# hw2.net
KiCad netlist of a schematic drawn in EAGLE
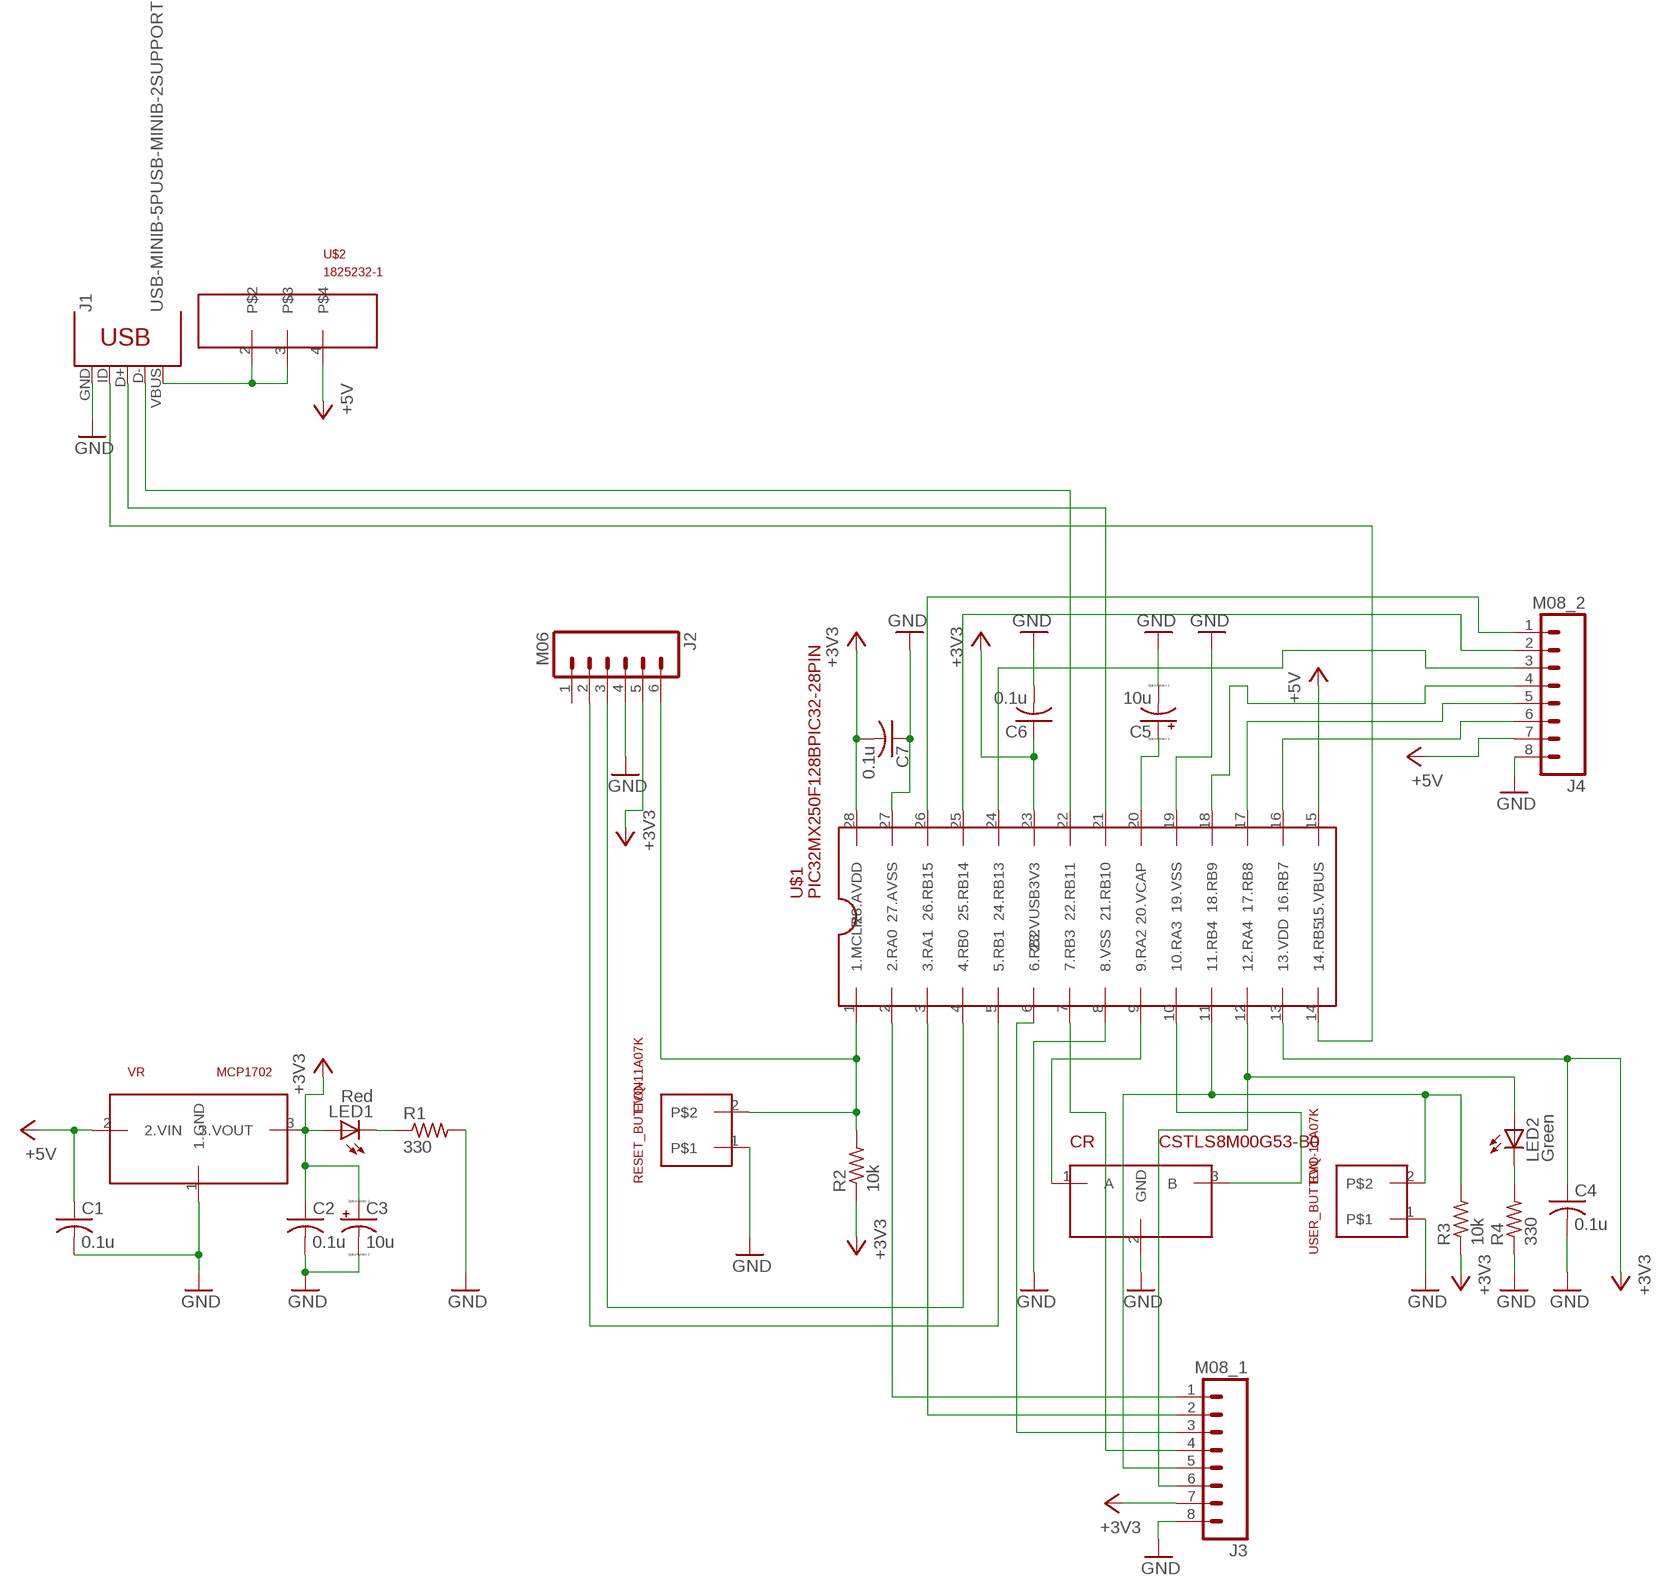
[diagram p0: schematic, sheet 1]

(export (version "E")
  (design (tool "Eeschema 10.0.6"))
  (components
    (comp (ref "C1")
      (value "0.1u")
      (footprint "eagle-import:C025-025X050")
      (libsource (lib "eagle-import") (part "C-US025-025X050"))
    )
    (comp (ref "C2")
      (value "0.1u")
      (footprint "eagle-import:C025-025X050")
      (libsource (lib "eagle-import") (part "C-US025-025X050"))
    )
    (comp (ref "C3")
      (value "10u")
      (footprint "eagle-import:B45181A")
      (libsource (lib "eagle-import") (part "CPOL-USB45181A"))
    )
    (comp (ref "C4")
      (value "0.1u")
      (footprint "eagle-import:C025-025X050")
      (libsource (lib "eagle-import") (part "C-US025-025X050"))
    )
    (comp (ref "C5")
      (value "10u")
      (footprint "eagle-import:B45181A")
      (libsource (lib "eagle-import") (part "CPOL-USB45181A"))
    )
    (comp (ref "C6")
      (value "0.1u")
      (footprint "eagle-import:C025-025X050")
      (libsource (lib "eagle-import") (part "C-US025-025X050"))
    )
    (comp (ref "C7")
      (value "0.1u")
      (footprint "eagle-import:C025-025X050")
      (libsource (lib "eagle-import") (part "C-US025-025X050"))
    )
    (comp (ref "CR")
      (value "CSTLS8M00G53-B0")
      (footprint "eagle-import:1X03_NO_SILK")
      (libsource (lib "eagle-import") (part "CSTLS8M00G53-B0"))
    )
    (comp (ref "J1")
      (value "USB-MINIB-5PUSB-MINIB-2SUPPORT")
      (footprint "eagle-import:USB-MB-H")
      (libsource (lib "eagle-import") (part "USB-MINIB-5PUSB-MINIB-2SUPPORT"))
    )
    (comp (ref "J2")
      (value "M06")
      (footprint "eagle-import:1X06")
      (libsource (lib "eagle-import") (part "M06SILK_FEMALE_PTH"))
    )
    (comp (ref "J3")
      (value "M08_1")
      (footprint "eagle-import:1X08_ROUND")
      (libsource (lib "eagle-import") (part "M08"))
    )
    (comp (ref "J4")
      (value "M08_2")
      (footprint "eagle-import:1X08_ROUND")
      (libsource (lib "eagle-import") (part "M08"))
    )
    (comp (ref "LED1")
      (value "Red")
      (footprint "eagle-import:LED3MM")
      (libsource (lib "eagle-import") (part "LED3MM"))
    )
    (comp (ref "LED2")
      (value "Green")
      (footprint "eagle-import:LED3MM")
      (libsource (lib "eagle-import") (part "LED3MM"))
    )
    (comp (ref "R1")
      (value "330")
      (footprint "eagle-import:0207_10")
      (libsource (lib "eagle-import") (part "R-US_0207/10"))
    )
    (comp (ref "R2")
      (value "10k")
      (footprint "eagle-import:0207_10")
      (libsource (lib "eagle-import") (part "R-US_0207/10"))
    )
    (comp (ref "R3")
      (value "10k")
      (footprint "eagle-import:0207_10")
      (libsource (lib "eagle-import") (part "R-US_0207/10"))
    )
    (comp (ref "R4")
      (value "330")
      (footprint "eagle-import:0207_10")
      (libsource (lib "eagle-import") (part "R-US_0207/10"))
    )
    (comp (ref "RESET_BUTTON")
      (value "EVQ-11A07K")
      (footprint "eagle-import:1X02_NO_SILK_FAR_BOUNDED")
      (libsource (lib "eagle-import") (part "EVQ-11A07K"))
    )
    (comp (ref "U$1")
      (value "PIC32MX250F128BPIC32-28PIN")
      (footprint "eagle-import:DIL28-3")
      (libsource (lib "eagle-import") (part "PIC32MX250F128BPIC32-28PIN"))
    )
    (comp (ref "U$2")
      (value "1825232-1")
      (footprint "eagle-import:1X05")
      (libsource (lib "eagle-import") (part "1825232-1"))
    )
    (comp (ref "USER_BUTTON")
      (value "EVQ-11A07K")
      (footprint "eagle-import:1X02_NO_SILK_FAR_BOUNDED")
      (libsource (lib "eagle-import") (part "EVQ-11A07K"))
    )
    (comp (ref "VR")
      (value "MCP1702")
      (footprint "eagle-import:TO92")
      (libsource (lib "eagle-import") (part "MCP1702"))
    )
  )
  (nets
    (net (code "1") (name "+3V3") (class "Default")
      (node (ref "C2") (pin "1") (pinfunction "1_1") (pintype "passive"))
      (node (ref "C3") (pin "+") (pinfunction "+_+") (pintype "passive"))
      (node (ref "C4") (pin "1") (pinfunction "1_1") (pintype "passive"))
      (node (ref "C6") (pin "1") (pinfunction "1_1") (pintype "passive"))
      (node (ref "C7") (pin "2") (pinfunction "2_2") (pintype "passive"))
      (node (ref "J2") (pin "5") (pinfunction "5_5") (pintype "passive"))
      (node (ref "J3") (pin "7") (pinfunction "7_7") (pintype "passive"))
      (node (ref "LED1") (pin "A") (pinfunction "A_A") (pintype "passive"))
      (node (ref "R2") (pin "1") (pinfunction "1_1") (pintype "passive"))
      (node (ref "R3") (pin "1") (pinfunction "1_1") (pintype "passive"))
      (node (ref "U$1") (pin "13") (pinfunction "13.VDD_13") (pintype "bidirectional"))
      (node (ref "U$1") (pin "23") (pinfunction "23.VUSB3V3_23") (pintype "bidirectional"))
      (node (ref "U$1") (pin "28") (pinfunction "28.AVDD_28") (pintype "bidirectional"))
      (node (ref "VR") (pin "3") (pinfunction "3.VOUT_3") (pintype "bidirectional"))
    )
    (net (code "2") (name "+5V") (class "Default")
      (node (ref "C1") (pin "1") (pinfunction "1_1") (pintype "passive"))
      (node (ref "J4") (pin "7") (pinfunction "7_7") (pintype "passive"))
      (node (ref "U$1") (pin "15") (pinfunction "15.VBUS_15") (pintype "bidirectional"))
      (node (ref "U$2") (pin "4") (pinfunction "P$4_4") (pintype "bidirectional"))
      (node (ref "VR") (pin "2") (pinfunction "2.VIN_2") (pintype "bidirectional"))
    )
    (net (code "3") (name "GND") (class "Default")
      (node (ref "C1") (pin "2") (pinfunction "2_2") (pintype "passive"))
      (node (ref "C2") (pin "2") (pinfunction "2_2") (pintype "passive"))
      (node (ref "C3") (pin "-") (pinfunction "-_-") (pintype "passive"))
      (node (ref "C4") (pin "2") (pinfunction "2_2") (pintype "passive"))
      (node (ref "C5") (pin "-") (pinfunction "-_-") (pintype "passive"))
      (node (ref "C6") (pin "2") (pinfunction "2_2") (pintype "passive"))
      (node (ref "C7") (pin "1") (pinfunction "1_1") (pintype "passive"))
      (node (ref "CR") (pin "2") (pinfunction "GND_2") (pintype "bidirectional"))
      (node (ref "J1") (pin "GND") (pinfunction "GND_GND") (pintype "bidirectional"))
      (node (ref "J2") (pin "4") (pinfunction "4_4") (pintype "passive"))
      (node (ref "J3") (pin "8") (pinfunction "8_8") (pintype "passive"))
      (node (ref "J4") (pin "8") (pinfunction "8_8") (pintype "passive"))
      (node (ref "R1") (pin "2") (pinfunction "2_2") (pintype "passive"))
      (node (ref "R4") (pin "1") (pinfunction "1_1") (pintype "passive"))
      (node (ref "RESET_BUTTON") (pin "1") (pinfunction "P$1_1") (pintype "bidirectional"))
      (node (ref "U$1") (pin "19") (pinfunction "19.VSS_19") (pintype "bidirectional"))
      (node (ref "U$1") (pin "27") (pinfunction "27.AVSS_27") (pintype "bidirectional"))
      (node (ref "U$1") (pin "8") (pinfunction "8.VSS_8") (pintype "bidirectional"))
      (node (ref "USER_BUTTON") (pin "1") (pinfunction "P$1_1") (pintype "bidirectional"))
      (node (ref "VR") (pin "1") (pinfunction "1.GND_1") (pintype "bidirectional"))
    )
    (net (code "4") (name "Net-(CR-A)") (class "Default")
      (node (ref "CR") (pin "1") (pinfunction "A_1") (pintype "bidirectional"))
      (node (ref "U$1") (pin "9") (pinfunction "9.RA2_9") (pintype "bidirectional"))
    )
    (net (code "5") (name "Net-(CR-B)") (class "Default")
      (node (ref "CR") (pin "3") (pinfunction "B_3") (pintype "bidirectional"))
      (node (ref "U$1") (pin "10") (pinfunction "10.RA3_10") (pintype "bidirectional"))
    )
    (net (code "6") (name "Net-(LED1-C)") (class "Default")
      (node (ref "LED1") (pin "K") (pinfunction "C_K") (pintype "passive"))
      (node (ref "R1") (pin "1") (pinfunction "1_1") (pintype "passive"))
    )
    (net (code "7") (name "Net-(LED2-C)") (class "Default")
      (node (ref "LED2") (pin "K") (pinfunction "C_K") (pintype "passive"))
      (node (ref "R4") (pin "2") (pinfunction "2_2") (pintype "passive"))
    )
    (net (code "8") (name "Net-(RESET_BUTTON-P$2)") (class "Default")
      (node (ref "J2") (pin "6") (pinfunction "6_6") (pintype "passive"))
      (node (ref "R2") (pin "2") (pinfunction "2_2") (pintype "passive"))
      (node (ref "RESET_BUTTON") (pin "2") (pinfunction "P$2_2") (pintype "bidirectional"))
      (node (ref "U$1") (pin "1") (pinfunction "1.MCLR_1") (pintype "bidirectional"))
    )
    (net (code "9") (name "Net-(U$1-2.RA0)") (class "Default")
      (node (ref "J3") (pin "1") (pinfunction "1_1") (pintype "passive"))
      (node (ref "U$1") (pin "2") (pinfunction "2.RA0_2") (pintype "bidirectional"))
    )
    (net (code "10") (name "Net-(U$1-3.RA1)") (class "Default")
      (node (ref "J3") (pin "2") (pinfunction "2_2") (pintype "passive"))
      (node (ref "U$1") (pin "3") (pinfunction "3.RA1_3") (pintype "bidirectional"))
    )
    (net (code "11") (name "Net-(U$1-4.RB0)") (class "Default")
      (node (ref "J2") (pin "3") (pinfunction "3_3") (pintype "passive"))
      (node (ref "U$1") (pin "4") (pinfunction "4.RB0_4") (pintype "bidirectional"))
    )
    (net (code "12") (name "Net-(U$1-5.RB1)") (class "Default")
      (node (ref "J2") (pin "2") (pinfunction "2_2") (pintype "passive"))
      (node (ref "U$1") (pin "5") (pinfunction "5.RB1_5") (pintype "bidirectional"))
    )
    (net (code "13") (name "Net-(U$1-6.RB2)") (class "Default")
      (node (ref "J3") (pin "3") (pinfunction "3_3") (pintype "passive"))
      (node (ref "U$1") (pin "6") (pinfunction "6.RB2_6") (pintype "bidirectional"))
    )
    (net (code "14") (name "Net-(U$1-7.RB3)") (class "Default")
      (node (ref "J3") (pin "4") (pinfunction "4_4") (pintype "passive"))
      (node (ref "U$1") (pin "7") (pinfunction "7.RB3_7") (pintype "bidirectional"))
    )
    (net (code "15") (name "Net-(U$1-11.RB4)") (class "Default")
      (node (ref "J3") (pin "5") (pinfunction "5_5") (pintype "passive"))
      (node (ref "R3") (pin "2") (pinfunction "2_2") (pintype "passive"))
      (node (ref "U$1") (pin "11") (pinfunction "11.RB4_11") (pintype "bidirectional"))
      (node (ref "USER_BUTTON") (pin "2") (pinfunction "P$2_2") (pintype "bidirectional"))
    )
    (net (code "16") (name "Net-(U$1-12.RA4)") (class "Default")
      (node (ref "J3") (pin "6") (pinfunction "6_6") (pintype "passive"))
      (node (ref "LED2") (pin "A") (pinfunction "A_A") (pintype "passive"))
      (node (ref "U$1") (pin "12") (pinfunction "12.RA4_12") (pintype "bidirectional"))
    )
    (net (code "17") (name "Net-(U$1-14.RB5)") (class "Default")
      (node (ref "J1") (pin "ID") (pinfunction "ID_ID") (pintype "bidirectional"))
      (node (ref "U$1") (pin "14") (pinfunction "14.RB5_14") (pintype "bidirectional"))
    )
    (net (code "18") (name "Net-(U$1-16.RB7)") (class "Default")
      (node (ref "J4") (pin "6") (pinfunction "6_6") (pintype "passive"))
      (node (ref "U$1") (pin "16") (pinfunction "16.RB7_16") (pintype "bidirectional"))
    )
    (net (code "19") (name "Net-(U$1-17.RB8)") (class "Default")
      (node (ref "J4") (pin "5") (pinfunction "5_5") (pintype "passive"))
      (node (ref "U$1") (pin "17") (pinfunction "17.RB8_17") (pintype "bidirectional"))
    )
    (net (code "20") (name "Net-(U$1-18.RB9)") (class "Default")
      (node (ref "J4") (pin "4") (pinfunction "4_4") (pintype "passive"))
      (node (ref "U$1") (pin "18") (pinfunction "18.RB9_18") (pintype "bidirectional"))
    )
    (net (code "21") (name "Net-(U$1-20.VCAP)") (class "Default")
      (node (ref "C5") (pin "+") (pinfunction "+_+") (pintype "passive"))
      (node (ref "U$1") (pin "20") (pinfunction "20.VCAP_20") (pintype "bidirectional"))
    )
    (net (code "22") (name "Net-(U$1-21.RB10)") (class "Default")
      (node (ref "J1") (pin "D+") (pinfunction "D+_D+") (pintype "bidirectional"))
      (node (ref "U$1") (pin "21") (pinfunction "21.RB10_21") (pintype "bidirectional"))
    )
    (net (code "23") (name "Net-(U$1-22.RB11)") (class "Default")
      (node (ref "J1") (pin "D-") (pinfunction "D-_D-") (pintype "bidirectional"))
      (node (ref "U$1") (pin "22") (pinfunction "22.RB11_22") (pintype "bidirectional"))
    )
    (net (code "24") (name "Net-(U$1-24.RB13)") (class "Default")
      (node (ref "J4") (pin "3") (pinfunction "3_3") (pintype "passive"))
      (node (ref "U$1") (pin "24") (pinfunction "24.RB13_24") (pintype "bidirectional"))
    )
    (net (code "25") (name "Net-(U$1-25.RB14)") (class "Default")
      (node (ref "J4") (pin "2") (pinfunction "2_2") (pintype "passive"))
      (node (ref "U$1") (pin "25") (pinfunction "25.RB14_25") (pintype "bidirectional"))
    )
    (net (code "26") (name "Net-(U$1-26.RB15)") (class "Default")
      (node (ref "J4") (pin "1") (pinfunction "1_1") (pintype "passive"))
      (node (ref "U$1") (pin "26") (pinfunction "26.RB15_26") (pintype "bidirectional"))
    )
    (net (code "27") (name "Net-(U$2-P$2)") (class "Default")
      (node (ref "J1") (pin "VBUS") (pinfunction "VBUS_VBUS") (pintype "bidirectional"))
      (node (ref "U$2") (pin "2") (pinfunction "P$2_2") (pintype "bidirectional"))
      (node (ref "U$2") (pin "3") (pinfunction "P$3_3") (pintype "bidirectional"))
    )
    (net (code "28") (name "unconnected-(J2-Pad1)") (class "Default")
      (node (ref "J2") (pin "1") (pinfunction "1_1") (pintype "passive"))
    )
  )
)
